# MP1477H_DCDC_5V.net
KiCad netlist of a schematic drawn in Altium Designer
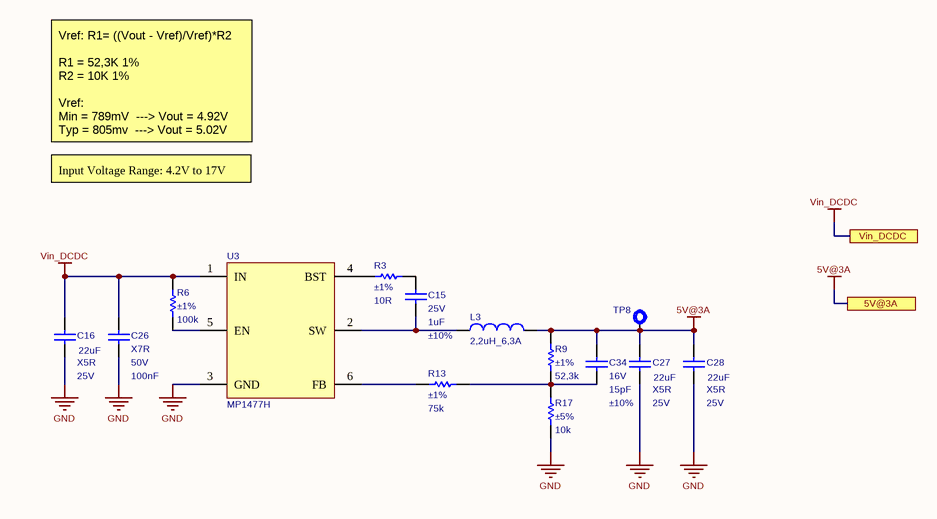
[diagram p0: MP1477H_DCDC_5V.SchDoc]

(export (version "E")
  (design (tool "Eeschema 10.0.6"))
  (components
    (comp (ref "C15")
      (value "C0603_1uF_25V_±10%")
      (footprint "C0603")
      (fields
        (field (name "VOLTAGE") "25V")
        (field (name "CAPACITANCE") "1uF")
        (field (name "TOLERANCE") "±10%")
        (field (name "MANUFACTURER") "Kemet")
      )
      (libsource (lib "BQ Vault") (part "Capacitor"))
    )
    (comp (ref "C16")
      (value "C1206_22uF_25V_±10%")
      (footprint "C1206")
      (fields
        (field (name "DIELECTRIC") "X5R")
        (field (name "VOLTAGE") "25V")
        (field (name "CAPACITANCE") "22uF")
        (field (name "TOLERANCE") "±10%")
        (field (name "MANUFACTURER") "Murata")
      )
      (libsource (lib "BQ Vault") (part "CMP-A0110-1"))
    )
    (comp (ref "C26")
      (value "C0603_100nF_50V_±10%_X7R")
      (footprint "C0603")
      (fields
        (field (name "DIELECTRIC") "X7R")
        (field (name "VOLTAGE") "50V")
        (field (name "CAPACITANCE") "100nF")
        (field (name "MANUFACTURER") "Kemet")
        (field (name "TOLERANCE") "±10%")
      )
      (libsource (lib "BQ Vault") (part "CMP-00257-1"))
    )
    (comp (ref "C27")
      (value "C1206_22uF_25V_±10%")
      (footprint "C1206")
      (fields
        (field (name "DIELECTRIC") "X5R")
        (field (name "VOLTAGE") "25V")
        (field (name "CAPACITANCE") "22uF")
        (field (name "TOLERANCE") "±10%")
        (field (name "MANUFACTURER") "Murata")
      )
      (libsource (lib "BQ Vault") (part "CMP-A0110-1"))
    )
    (comp (ref "C28")
      (value "C1206_22uF_25V_±10%")
      (footprint "C1206")
      (fields
        (field (name "DIELECTRIC") "X5R")
        (field (name "VOLTAGE") "25V")
        (field (name "CAPACITANCE") "22uF")
        (field (name "TOLERANCE") "±10%")
        (field (name "MANUFACTURER") "Murata")
      )
      (libsource (lib "BQ Vault") (part "CMP-A0110-1"))
    )
    (comp (ref "C34")
      (value "C0402_15pF_16V_±10%_C0G")
      (footprint "C0402")
      (fields
        (field (name "VOLTAGE") "16V")
        (field (name "CAPACITANCE") "15pF")
        (field (name "PART NUMBER") "C0402_15pF_16V_±10%")
        (field (name "TOLERANCE") "±10%")
        (field (name "MANUFACTURER") "Kemet")
      )
      (libsource (lib "BQ Vault") (part "Capacitor"))
    )
    (comp (ref "L3")
      (value "2,2uH_6,3A")
      (footprint "SRN8040")
      (description "Semi-shielded power inductor")
      (fields (field (name "MANUFACTURER") "Bourns"))
      (libsource (lib "BQ Vault") (part "Inductor"))
    )
    (comp (ref "R3")
      (value "R0402_10R_0.063W_±1%")
      (footprint "R0402")
      (fields
        (field (name "TOLERANCE") "±1%")
        (field (name "POWER") "0.063W")
        (field (name "RESISTANCE") "10R")
        (field (name "MANUFACTURER") "Vishay")
      )
      (libsource (lib "BQ Vault") (part "Resistor"))
    )
    (comp (ref "R6")
      (value "R0402_100k_0.063W_±1%")
      (footprint "R0402")
      (fields
        (field (name "TOLERANCE") "±1%")
        (field (name "POWER") "0.063W")
        (field (name "RESISTANCE") "100k")
        (field (name "MANUFACTURER") "Vishay")
      )
      (libsource (lib "BQ Vault") (part "Resistor"))
    )
    (comp (ref "R9")
      (value "R0402_52,3k_0.063W_±1%")
      (footprint "R0402")
      (fields
        (field (name "TOLERANCE") "±1%")
        (field (name "POWER") "0.063W")
        (field (name "RESISTANCE") "52,3k")
        (field (name "MANUFACTURER") "Vishay")
      )
      (libsource (lib "BQ Vault") (part "Resistor"))
    )
    (comp (ref "R13")
      (value "R0402_75k_0.063W_±1%")
      (footprint "R0402")
      (fields
        (field (name "TOLERANCE") "±1%")
        (field (name "POWER") "0.063W")
        (field (name "RESISTANCE") "75k")
        (field (name "MANUFACTURER") "Vishay")
      )
      (libsource (lib "BQ Vault") (part "Resistor"))
    )
    (comp (ref "R17")
      (value "R0402_10k_0.063W_±5%")
      (footprint "R0402")
      (fields
        (field (name "TOLERANCE") "±5%")
        (field (name "POWER") "0.063W")
        (field (name "RESISTANCE") "10k")
        (field (name "MANUFACTURER") "Vishay")
      )
      (libsource (lib "BQ Vault") (part "CMP-A1692-4"))
    )
    (comp (ref "TP8")
      (value "TP")
      (footprint "TP_POWER")
      (description "Testpoint 0.3mm")
      (fields (field (name "MANUFACTURER") "Oxley") (field (name "PART NUMBER") "TP_POWER"))
      (libsource (lib "BQ Vault") (part "CMP-A2499-3"))
    )
    (comp (ref "U3")
      (value "MP1477H")
      (footprint "SOT-563 - MP1477H")
      (description "DCDC Step Down Vout= 1-5V; Vin= 12-17V")
      (fields (field (name "MANUFACTURER") "MPS") (field (name "PART NUMBER") "MP1477GTF-Z"))
      (libsource (lib "BQ Vault") (part "MP1477H"))
    )
  )
  (nets
    (net (code "1") (name "5V@3A") (class "Default")
      (node (ref "C27") (pin "2") (pinfunction "2_2") (pintype "passive"))
      (node (ref "C28") (pin "2") (pinfunction "2_2") (pintype "passive"))
      (node (ref "C34") (pin "2") (pinfunction "2_2") (pintype "passive"))
      (node (ref "L3") (pin "2") (pinfunction "2_2") (pintype "passive"))
      (node (ref "R9") (pin "1") (pinfunction "1_1") (pintype "passive"))
      (node (ref "TP8") (pin "1") (pinfunction "1_1") (pintype "passive"))
    )
    (net (code "2") (name "GND") (class "Default")
      (node (ref "C16") (pin "1") (pinfunction "1_1") (pintype "passive"))
      (node (ref "C26") (pin "1") (pinfunction "1_1") (pintype "passive"))
      (node (ref "C27") (pin "1") (pinfunction "1_1") (pintype "passive"))
      (node (ref "C28") (pin "1") (pinfunction "1_1") (pintype "passive"))
      (node (ref "R17") (pin "2") (pinfunction "2_2") (pintype "passive"))
      (node (ref "U3") (pin "3") (pinfunction "GND_3") (pintype "passive"))
    )
    (net (code "3") (name "Net-(C15-Pad2)") (class "Default")
      (node (ref "C15") (pin "2") (pinfunction "2_2") (pintype "passive"))
      (node (ref "R3") (pin "2") (pinfunction "2_2") (pintype "passive"))
    )
    (net (code "4") (name "Net-(C34-Pad1)") (class "Default")
      (node (ref "C34") (pin "1") (pinfunction "1_1") (pintype "passive"))
      (node (ref "R13") (pin "2") (pinfunction "2_2") (pintype "passive"))
      (node (ref "R17") (pin "1") (pinfunction "1_1") (pintype "passive"))
      (node (ref "R9") (pin "2") (pinfunction "2_2") (pintype "passive"))
    )
    (net (code "5") (name "Net-(U3-BST)") (class "Default")
      (node (ref "R3") (pin "1") (pinfunction "1_1") (pintype "passive"))
      (node (ref "U3") (pin "4") (pinfunction "BST_4") (pintype "passive"))
    )
    (net (code "6") (name "Net-(U3-EN)") (class "Default")
      (node (ref "R6") (pin "1") (pinfunction "1_1") (pintype "passive"))
      (node (ref "U3") (pin "5") (pinfunction "EN_5") (pintype "passive"))
    )
    (net (code "7") (name "Net-(U3-FB)") (class "Default")
      (node (ref "R13") (pin "1") (pinfunction "1_1") (pintype "passive"))
      (node (ref "U3") (pin "6") (pinfunction "FB_6") (pintype "passive"))
    )
    (net (code "8") (name "Net-(U3-SW)") (class "Default")
      (node (ref "C15") (pin "1") (pinfunction "1_1") (pintype "passive"))
      (node (ref "L3") (pin "1") (pinfunction "1_1") (pintype "passive"))
      (node (ref "U3") (pin "2") (pinfunction "SW_2") (pintype "passive"))
    )
    (net (code "9") (name "Vin_DCDC") (class "Default")
      (node (ref "C16") (pin "2") (pinfunction "2_2") (pintype "passive"))
      (node (ref "C26") (pin "2") (pinfunction "2_2") (pintype "passive"))
      (node (ref "R6") (pin "2") (pinfunction "2_2") (pintype "passive"))
      (node (ref "U3") (pin "1") (pinfunction "IN_1") (pintype "passive"))
    )
  )
)
